# v5_mainboard_omega.net
KiCad netlist of a schematic drawn in EAGLE
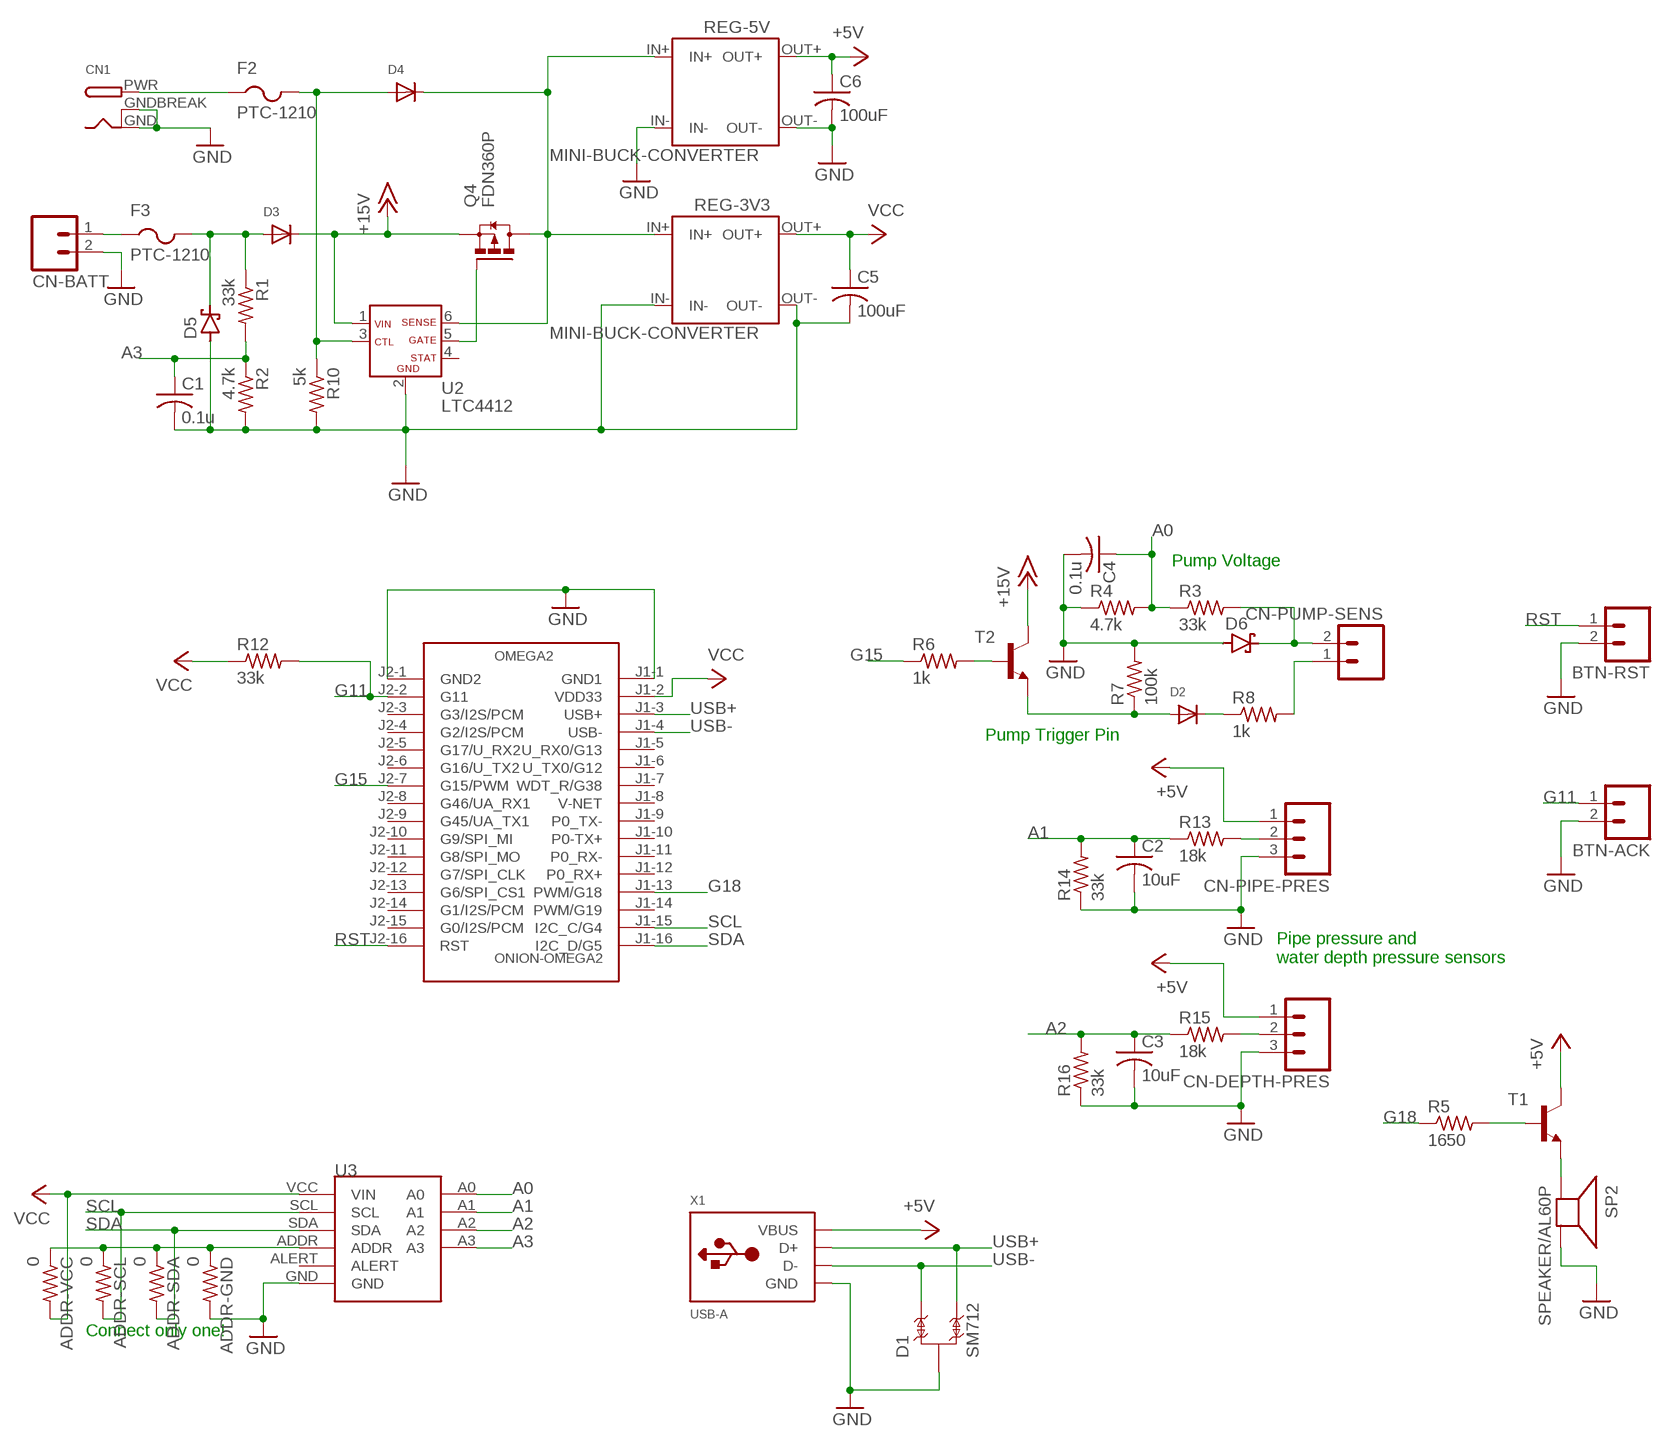
[diagram p0: schematic, sheet 1]

(export (version "E")
  (design (tool "Eeschema 10.0.6"))
  (components
    (comp (ref "ADDR-GND")
      (value "0")
      (footprint "eagle-import:R0603")
      (libsource (lib "eagle-import") (part "R-US_R0603"))
    )
    (comp (ref "ADDR-SCL")
      (value "0")
      (footprint "eagle-import:R0603")
      (libsource (lib "eagle-import") (part "R-US_R0603"))
    )
    (comp (ref "ADDR-SDA")
      (value "0")
      (footprint "eagle-import:R0603")
      (libsource (lib "eagle-import") (part "R-US_R0603"))
    )
    (comp (ref "ADDR-VCC")
      (value "0")
      (footprint "eagle-import:R0603")
      (libsource (lib "eagle-import") (part "R-US_R0603"))
    )
    (comp (ref "BTN-ACK")
      (value "M02")
      (footprint "eagle-import:02P")
      (libsource (lib "eagle-import") (part "M02"))
    )
    (comp (ref "BTN-RST")
      (value "M02")
      (footprint "eagle-import:02P")
      (libsource (lib "eagle-import") (part "M02"))
    )
    (comp (ref "C1")
      (value "0.1u")
      (footprint "eagle-import:C0603K")
      (libsource (lib "eagle-import") (part "C-USC0603K"))
    )
    (comp (ref "C2")
      (value "10uF")
      (footprint "eagle-import:C0805K")
      (libsource (lib "eagle-import") (part "C-USC0805K"))
    )
    (comp (ref "C3")
      (value "10uF")
      (footprint "eagle-import:C0805K")
      (libsource (lib "eagle-import") (part "C-USC0805K"))
    )
    (comp (ref "C4")
      (value "0.1u")
      (footprint "eagle-import:C0603K")
      (libsource (lib "eagle-import") (part "C-USC0603K"))
    )
    (comp (ref "C5")
      (value "100uF")
      (footprint "eagle-import:C2220K")
      (libsource (lib "eagle-import") (part "C-USC2220K"))
    )
    (comp (ref "C6")
      (value "100uF")
      (footprint "eagle-import:C2220K")
      (libsource (lib "eagle-import") (part "C-USC2220K"))
    )
    (comp (ref "CN-BATT")
      (value "M02")
      (footprint "eagle-import:02P")
      (libsource (lib "eagle-import") (part "M02"))
    )
    (comp (ref "CN-DEPTH-PRES")
      (value "M03")
      (footprint "eagle-import:03P")
      (libsource (lib "eagle-import") (part "M03"))
    )
    (comp (ref "CN-PIPE-PRES")
      (value "M03")
      (footprint "eagle-import:03P")
      (libsource (lib "eagle-import") (part "M03"))
    )
    (comp (ref "CN-PUMP-SENS")
      (value "M02")
      (footprint "eagle-import:02P")
      (libsource (lib "eagle-import") (part "M02"))
    )
    (comp (ref "CN1")
      (value "DCBARRELPTH")
      (footprint "eagle-import:DCJACK_2MM_PTH")
      (libsource (lib "eagle-import") (part "DCBARRELPTH"))
    )
    (comp (ref "D1")
      (value "SM712")
      (footprint "eagle-import:SOT23-3")
      (libsource (lib "eagle-import") (part "SM712"))
    )
    (comp (ref "D2")
      (value "DIODESMA")
      (footprint "eagle-import:SMADIODE")
      (libsource (lib "eagle-import") (part "DIODESMA"))
    )
    (comp (ref "D3")
      (value "DIODESMA")
      (footprint "eagle-import:SMADIODE")
      (libsource (lib "eagle-import") (part "DIODESMA"))
    )
    (comp (ref "D4")
      (value "DIODESMA")
      (footprint "eagle-import:SMADIODE")
      (libsource (lib "eagle-import") (part "DIODESMA"))
    )
    (comp (ref "D5")
      (value "SCHOTTKY-DIODESMC")
      (footprint "eagle-import:SMC")
      (libsource (lib "eagle-import") (part "SCHOTTKY-DIODESMC"))
    )
    (comp (ref "D6")
      (value "SCHOTTKY-DIODESMC")
      (footprint "eagle-import:SMC")
      (libsource (lib "eagle-import") (part "SCHOTTKY-DIODESMC"))
    )
    (comp (ref "F2")
      (value "PTC-1210")
      (footprint "eagle-import:1210")
      (libsource (lib "eagle-import") (part "PTC-1210"))
    )
    (comp (ref "F3")
      (value "PTC-1210")
      (footprint "eagle-import:1210")
      (libsource (lib "eagle-import") (part "PTC-1210"))
    )
    (comp (ref "OMEGA2")
      (value "ONION-OMEGA2")
      (footprint "eagle-import:ONION-2MM-2X16")
      (libsource (lib "eagle-import") (part "ONION-OMEGA2"))
    )
    (comp (ref "Q4")
      (value "FDN360P")
      (footprint "eagle-import:SUPER-SOT3")
      (libsource (lib "eagle-import") (part "FDN360P"))
    )
    (comp (ref "R1")
      (value "33k")
      (footprint "eagle-import:R0603")
      (libsource (lib "eagle-import") (part "R-US_R0603"))
    )
    (comp (ref "R2")
      (value "4.7k")
      (footprint "eagle-import:R0603")
      (libsource (lib "eagle-import") (part "R-US_R0603"))
    )
    (comp (ref "R3")
      (value "33k")
      (footprint "eagle-import:R0603")
      (libsource (lib "eagle-import") (part "R-US_R0603"))
    )
    (comp (ref "R4")
      (value "4.7k")
      (footprint "eagle-import:R0603")
      (libsource (lib "eagle-import") (part "R-US_R0603"))
    )
    (comp (ref "R5")
      (value "1650")
      (footprint "eagle-import:R0603")
      (libsource (lib "eagle-import") (part "R-US_R0603"))
    )
    (comp (ref "R6")
      (value "1k")
      (footprint "eagle-import:R0603")
      (libsource (lib "eagle-import") (part "R-US_R0603"))
    )
    (comp (ref "R7")
      (value "100k")
      (footprint "eagle-import:R0603")
      (libsource (lib "eagle-import") (part "R-US_R0603"))
    )
    (comp (ref "R8")
      (value "1k")
      (footprint "eagle-import:R0603")
      (libsource (lib "eagle-import") (part "R-US_R0603"))
    )
    (comp (ref "R10")
      (value "5k")
      (footprint "eagle-import:R0603")
      (libsource (lib "eagle-import") (part "R-US_R0603"))
    )
    (comp (ref "R12")
      (value "33k")
      (footprint "eagle-import:R0603")
      (libsource (lib "eagle-import") (part "R-US_R0603"))
    )
    (comp (ref "R13")
      (value "18k")
      (footprint "eagle-import:R0603")
      (libsource (lib "eagle-import") (part "R-US_R0603"))
    )
    (comp (ref "R14")
      (value "33k")
      (footprint "eagle-import:R0603")
      (libsource (lib "eagle-import") (part "R-US_R0603"))
    )
    (comp (ref "R15")
      (value "18k")
      (footprint "eagle-import:R0603")
      (libsource (lib "eagle-import") (part "R-US_R0603"))
    )
    (comp (ref "R16")
      (value "33k")
      (footprint "eagle-import:R0603")
      (libsource (lib "eagle-import") (part "R-US_R0603"))
    )
    (comp (ref "REG-3V3")
      (value "MINI-BUCK-CONVERTER")
      (footprint "eagle-import:MINI-BUCK-CONVERTER")
      (libsource (lib "eagle-import") (part "MINI-BUCK-CONVERTER"))
    )
    (comp (ref "REG-5V")
      (value "MINI-BUCK-CONVERTER")
      (footprint "eagle-import:MINI-BUCK-CONVERTER")
      (libsource (lib "eagle-import") (part "MINI-BUCK-CONVERTER"))
    )
    (comp (ref "SP2")
      (value "SPEAKER/AL60P")
      (footprint "eagle-import:AL60P")
      (libsource (lib "eagle-import") (part "SPEAKER/AL60P"))
    )
    (comp (ref "T1")
      (value "BC808-NPN-SOT23-BEC")
      (footprint "eagle-import:SOT23-BEC")
      (libsource (lib "eagle-import") (part "-NPN-SOT23-BECBC808"))
    )
    (comp (ref "T2")
      (value "BC808-NPN-SOT23-BEC")
      (footprint "eagle-import:SOT23-BEC")
      (libsource (lib "eagle-import") (part "-NPN-SOT23-BECBC808"))
    )
    (comp (ref "U2")
      (value "LTC4412")
      (footprint "eagle-import:SOT23-6")
      (libsource (lib "eagle-import") (part "LTC4412"))
    )
    (comp (ref "U3")
      (value "GY-ADS1115THM")
      (footprint "eagle-import:GY-ADS1115-THM")
      (libsource (lib "eagle-import") (part "GY-ADS1115THM"))
    )
    (comp (ref "X1")
      (value "USB-A")
      (footprint "eagle-import:MOLEX_480371000")
      (libsource (lib "eagle-import") (part "USB-A"))
    )
  )
  (nets
    (net (code "1") (name "+5V") (class "Default")
      (node (ref "C6") (pin "1") (pinfunction "1_1") (pintype "passive"))
      (node (ref "CN-DEPTH-PRES") (pin "1") (pinfunction "1_1") (pintype "passive"))
      (node (ref "CN-PIPE-PRES") (pin "1") (pinfunction "1_1") (pintype "passive"))
      (node (ref "REG-5V") (pin "OUT+") (pinfunction "OUT+_OUT+") (pintype "power_in"))
      (node (ref "T1") (pin "C") (pinfunction "C_C") (pintype "passive"))
      (node (ref "X1") (pin "1") (pinfunction "VBUS_1") (pintype "power_in"))
    )
    (net (code "2") (name "+15V") (class "Default")
      (node (ref "D3") (pin "C") (pinfunction "C_C") (pintype "passive"))
      (node (ref "Q4") (pin "2") (pinfunction "S_2") (pintype "passive"))
      (node (ref "T2") (pin "C") (pinfunction "C_C") (pintype "passive"))
      (node (ref "U2") (pin "1") (pinfunction "VIN_1") (pintype "power_in"))
    )
    (net (code "3") (name "/A0") (class "Default")
      (node (ref "C4") (pin "1") (pinfunction "1_1") (pintype "passive"))
      (node (ref "R3") (pin "1") (pinfunction "1_1") (pintype "passive"))
      (node (ref "R4") (pin "2") (pinfunction "2_2") (pintype "passive"))
      (node (ref "U3") (pin "A0") (pinfunction "A0_A0") (pintype "bidirectional"))
    )
    (net (code "4") (name "/A1") (class "Default")
      (node (ref "C2") (pin "1") (pinfunction "1_1") (pintype "passive"))
      (node (ref "R13") (pin "1") (pinfunction "1_1") (pintype "passive"))
      (node (ref "R14") (pin "2") (pinfunction "2_2") (pintype "passive"))
      (node (ref "U3") (pin "A1") (pinfunction "A1_A1") (pintype "bidirectional"))
    )
    (net (code "5") (name "/A2") (class "Default")
      (node (ref "C3") (pin "1") (pinfunction "1_1") (pintype "passive"))
      (node (ref "R15") (pin "1") (pinfunction "1_1") (pintype "passive"))
      (node (ref "R16") (pin "2") (pinfunction "2_2") (pintype "passive"))
      (node (ref "U3") (pin "A2") (pinfunction "A2_A2") (pintype "bidirectional"))
    )
    (net (code "6") (name "/A3") (class "Default")
      (node (ref "C1") (pin "1") (pinfunction "1_1") (pintype "passive"))
      (node (ref "R1") (pin "2") (pinfunction "2_2") (pintype "passive"))
      (node (ref "R2") (pin "1") (pinfunction "1_1") (pintype "passive"))
      (node (ref "U3") (pin "A3") (pinfunction "A3_A3") (pintype "bidirectional"))
    )
    (net (code "7") (name "/G11") (class "Default")
      (node (ref "BTN-ACK") (pin "1") (pinfunction "1_1") (pintype "passive"))
      (node (ref "OMEGA2") (pin "J2-2") (pinfunction "G11_J2-2") (pintype "bidirectional"))
      (node (ref "R12") (pin "2") (pinfunction "2_2") (pintype "passive"))
    )
    (net (code "8") (name "/G15") (class "Default")
      (node (ref "OMEGA2") (pin "J2-7") (pinfunction "G15/PWM_J2-7") (pintype "bidirectional"))
      (node (ref "R6") (pin "1") (pinfunction "1_1") (pintype "passive"))
    )
    (net (code "9") (name "/G18") (class "Default")
      (node (ref "OMEGA2") (pin "J1-13") (pinfunction "PWM/G18_J1-13") (pintype "bidirectional"))
      (node (ref "R5") (pin "1") (pinfunction "1_1") (pintype "passive"))
    )
    (net (code "10") (name "/RST") (class "Default")
      (node (ref "BTN-RST") (pin "1") (pinfunction "1_1") (pintype "passive"))
      (node (ref "OMEGA2") (pin "J2-16") (pinfunction "RST_J2-16") (pintype "bidirectional"))
    )
    (net (code "11") (name "/SCL") (class "Default")
      (node (ref "ADDR-SCL") (pin "2") (pinfunction "2_2") (pintype "passive"))
      (node (ref "OMEGA2") (pin "J1-15") (pinfunction "I2C_C/G4_J1-15") (pintype "bidirectional"))
      (node (ref "U3") (pin "SCL") (pinfunction "SCL_SCL") (pintype "bidirectional"))
    )
    (net (code "12") (name "/SDA") (class "Default")
      (node (ref "ADDR-SDA") (pin "2") (pinfunction "2_2") (pintype "passive"))
      (node (ref "OMEGA2") (pin "J1-16") (pinfunction "I2C_D/G5_J1-16") (pintype "bidirectional"))
      (node (ref "U3") (pin "SDA") (pinfunction "SDA_SDA") (pintype "bidirectional"))
    )
    (net (code "13") (name "/USB+") (class "Default")
      (node (ref "D1") (pin "1") (pinfunction "1_1") (pintype "passive"))
      (node (ref "OMEGA2") (pin "J1-3") (pinfunction "USB+_J1-3") (pintype "bidirectional"))
      (node (ref "X1") (pin "3") (pinfunction "D+_3") (pintype "bidirectional"))
    )
    (net (code "14") (name "/USB-") (class "Default")
      (node (ref "D1") (pin "2") (pinfunction "2_2") (pintype "passive"))
      (node (ref "OMEGA2") (pin "J1-4") (pinfunction "USB-_J1-4") (pintype "bidirectional"))
      (node (ref "X1") (pin "2") (pinfunction "D-_2") (pintype "bidirectional"))
    )
    (net (code "15") (name "GND") (class "Default")
      (node (ref "ADDR-GND") (pin "2") (pinfunction "2_2") (pintype "passive"))
      (node (ref "BTN-ACK") (pin "2") (pinfunction "2_2") (pintype "passive"))
      (node (ref "BTN-RST") (pin "2") (pinfunction "2_2") (pintype "passive"))
      (node (ref "C1") (pin "2") (pinfunction "2_2") (pintype "passive"))
      (node (ref "C2") (pin "2") (pinfunction "2_2") (pintype "passive"))
      (node (ref "C3") (pin "2") (pinfunction "2_2") (pintype "passive"))
      (node (ref "C4") (pin "2") (pinfunction "2_2") (pintype "passive"))
      (node (ref "C5") (pin "2") (pinfunction "2_2") (pintype "passive"))
      (node (ref "C6") (pin "2") (pinfunction "2_2") (pintype "passive"))
      (node (ref "CN-BATT") (pin "2") (pinfunction "2_2") (pintype "passive"))
      (node (ref "CN-DEPTH-PRES") (pin "3") (pinfunction "3_3") (pintype "passive"))
      (node (ref "CN-PIPE-PRES") (pin "3") (pinfunction "3_3") (pintype "passive"))
      (node (ref "CN1") (pin "GND") (pinfunction "GND_GND") (pintype "power_in"))
      (node (ref "CN1") (pin "GNDBREAK") (pinfunction "GNDBREAK_GNDBREAK") (pintype "power_in"))
      (node (ref "D1") (pin "3") (pinfunction "3_3") (pintype "passive"))
      (node (ref "D5") (pin "A") (pinfunction "A_A") (pintype "passive"))
      (node (ref "D6") (pin "A") (pinfunction "A_A") (pintype "passive"))
      (node (ref "OMEGA2") (pin "J1-1") (pinfunction "GND1_J1-1") (pintype "bidirectional"))
      (node (ref "OMEGA2") (pin "J2-1") (pinfunction "GND2_J2-1") (pintype "bidirectional"))
      (node (ref "R10") (pin "2") (pinfunction "2_2") (pintype "passive"))
      (node (ref "R14") (pin "1") (pinfunction "1_1") (pintype "passive"))
      (node (ref "R16") (pin "1") (pinfunction "1_1") (pintype "passive"))
      (node (ref "R2") (pin "2") (pinfunction "2_2") (pintype "passive"))
      (node (ref "R4") (pin "1") (pinfunction "1_1") (pintype "passive"))
      (node (ref "R7") (pin "2") (pinfunction "2_2") (pintype "passive"))
      (node (ref "REG-3V3") (pin "IN-") (pinfunction "IN-_IN-") (pintype "power_in"))
      (node (ref "REG-3V3") (pin "OUT-") (pinfunction "OUT-_OUT-") (pintype "power_in"))
      (node (ref "REG-5V") (pin "IN-") (pinfunction "IN-_IN-") (pintype "power_in"))
      (node (ref "REG-5V") (pin "OUT-") (pinfunction "OUT-_OUT-") (pintype "power_in"))
      (node (ref "SP2") (pin "2") (pinfunction "-_2") (pintype "passive"))
      (node (ref "U2") (pin "2") (pinfunction "GND_2") (pintype "power_in"))
      (node (ref "U3") (pin "GND") (pinfunction "GND_GND") (pintype "bidirectional"))
      (node (ref "X1") (pin "4") (pinfunction "GND_4") (pintype "power_in"))
    )
    (net (code "16") (name "Net-(ADDR-GND-Pad1)") (class "Default")
      (node (ref "ADDR-GND") (pin "1") (pinfunction "1_1") (pintype "passive"))
      (node (ref "ADDR-SCL") (pin "1") (pinfunction "1_1") (pintype "passive"))
      (node (ref "ADDR-SDA") (pin "1") (pinfunction "1_1") (pintype "passive"))
      (node (ref "ADDR-VCC") (pin "1") (pinfunction "1_1") (pintype "passive"))
      (node (ref "U3") (pin "ADDR") (pinfunction "ADDR_ADDR") (pintype "bidirectional"))
    )
    (net (code "17") (name "Net-(CN-BATT-Pad1)") (class "Default")
      (node (ref "CN-BATT") (pin "1") (pinfunction "1_1") (pintype "passive"))
      (node (ref "F3") (pin "1") (pinfunction "1_1") (pintype "passive"))
    )
    (net (code "18") (name "Net-(CN-DEPTH-PRES-Pad2)") (class "Default")
      (node (ref "CN-DEPTH-PRES") (pin "2") (pinfunction "2_2") (pintype "passive"))
      (node (ref "R15") (pin "2") (pinfunction "2_2") (pintype "passive"))
    )
    (net (code "19") (name "Net-(CN-PIPE-PRES-Pad2)") (class "Default")
      (node (ref "CN-PIPE-PRES") (pin "2") (pinfunction "2_2") (pintype "passive"))
      (node (ref "R13") (pin "2") (pinfunction "2_2") (pintype "passive"))
    )
    (net (code "20") (name "Net-(CN-PUMP-SENS-Pad1)") (class "Default")
      (node (ref "CN-PUMP-SENS") (pin "1") (pinfunction "1_1") (pintype "passive"))
      (node (ref "R8") (pin "2") (pinfunction "2_2") (pintype "passive"))
    )
    (net (code "21") (name "Net-(CN-PUMP-SENS-Pad2)") (class "Default")
      (node (ref "CN-PUMP-SENS") (pin "2") (pinfunction "2_2") (pintype "passive"))
      (node (ref "D6") (pin "C") (pinfunction "C_C") (pintype "passive"))
      (node (ref "R3") (pin "2") (pinfunction "2_2") (pintype "passive"))
    )
    (net (code "22") (name "Net-(CN1-PadPWR)") (class "Default")
      (node (ref "CN1") (pin "PWR") (pinfunction "PWR_PWR") (pintype "power_in"))
      (node (ref "F2") (pin "1") (pinfunction "1_1") (pintype "passive"))
    )
    (net (code "23") (name "Net-(D2-PadA)") (class "Default")
      (node (ref "D2") (pin "A") (pinfunction "A_A") (pintype "passive"))
      (node (ref "R7") (pin "1") (pinfunction "1_1") (pintype "passive"))
      (node (ref "T2") (pin "E") (pinfunction "E_E") (pintype "passive"))
    )
    (net (code "24") (name "Net-(D2-PadC)") (class "Default")
      (node (ref "D2") (pin "C") (pinfunction "C_C") (pintype "passive"))
      (node (ref "R8") (pin "1") (pinfunction "1_1") (pintype "passive"))
    )
    (net (code "25") (name "Net-(D3-PadA)") (class "Default")
      (node (ref "D3") (pin "A") (pinfunction "A_A") (pintype "passive"))
      (node (ref "D5") (pin "C") (pinfunction "C_C") (pintype "passive"))
      (node (ref "F3") (pin "2") (pinfunction "2_2") (pintype "passive"))
      (node (ref "R1") (pin "1") (pinfunction "1_1") (pintype "passive"))
    )
    (net (code "26") (name "Net-(Q4-D)") (class "Default")
      (node (ref "D4") (pin "C") (pinfunction "C_C") (pintype "passive"))
      (node (ref "Q4") (pin "3") (pinfunction "D_3") (pintype "passive"))
      (node (ref "REG-3V3") (pin "IN+") (pinfunction "IN+_IN+") (pintype "power_in"))
      (node (ref "REG-5V") (pin "IN+") (pinfunction "IN+_IN+") (pintype "power_in"))
      (node (ref "U2") (pin "6") (pinfunction "SENSE_6") (pintype "input"))
    )
    (net (code "27") (name "Net-(Q4-G)") (class "Default")
      (node (ref "Q4") (pin "1") (pinfunction "G_1") (pintype "passive"))
      (node (ref "U2") (pin "5") (pinfunction "GATE_5") (pintype "output"))
    )
    (net (code "28") (name "Net-(R5-Pad2)") (class "Default")
      (node (ref "R5") (pin "2") (pinfunction "2_2") (pintype "passive"))
      (node (ref "T1") (pin "B") (pinfunction "B_B") (pintype "passive"))
    )
    (net (code "29") (name "Net-(R6-Pad2)") (class "Default")
      (node (ref "R6") (pin "2") (pinfunction "2_2") (pintype "passive"))
      (node (ref "T2") (pin "B") (pinfunction "B_B") (pintype "passive"))
    )
    (net (code "30") (name "Net-(SP2-+)") (class "Default")
      (node (ref "SP2") (pin "1") (pinfunction "+_1") (pintype "passive"))
      (node (ref "T1") (pin "E") (pinfunction "E_E") (pintype "passive"))
    )
    (net (code "31") (name "Net-(U2-CTL)") (class "Default")
      (node (ref "D4") (pin "A") (pinfunction "A_A") (pintype "passive"))
      (node (ref "F2") (pin "2") (pinfunction "2_2") (pintype "passive"))
      (node (ref "R10") (pin "1") (pinfunction "1_1") (pintype "passive"))
      (node (ref "U2") (pin "3") (pinfunction "CTL_3") (pintype "input"))
    )
    (net (code "32") (name "VCC") (class "Default")
      (node (ref "ADDR-VCC") (pin "2") (pinfunction "2_2") (pintype "passive"))
      (node (ref "C5") (pin "1") (pinfunction "1_1") (pintype "passive"))
      (node (ref "OMEGA2") (pin "J1-2") (pinfunction "VDD33_J1-2") (pintype "bidirectional"))
      (node (ref "R12") (pin "1") (pinfunction "1_1") (pintype "passive"))
      (node (ref "REG-3V3") (pin "OUT+") (pinfunction "OUT+_OUT+") (pintype "power_in"))
      (node (ref "U3") (pin "VCC") (pinfunction "VIN_VCC") (pintype "bidirectional"))
    )
    (net (code "33") (name "unconnected-(OMEGA2-G0{slash}I2S{slash}PCM-PadJ2-15)") (class "Default")
      (node (ref "OMEGA2") (pin "J2-15") (pinfunction "G0/I2S/PCM_J2-15") (pintype "bidirectional"))
    )
    (net (code "34") (name "unconnected-(OMEGA2-G1{slash}I2S{slash}PCM-PadJ2-14)") (class "Default")
      (node (ref "OMEGA2") (pin "J2-14") (pinfunction "G1/I2S/PCM_J2-14") (pintype "bidirectional"))
    )
    (net (code "35") (name "unconnected-(OMEGA2-G2{slash}I2S{slash}PCM-PadJ2-4)") (class "Default")
      (node (ref "OMEGA2") (pin "J2-4") (pinfunction "G2/I2S/PCM_J2-4") (pintype "bidirectional"))
    )
    (net (code "36") (name "unconnected-(OMEGA2-G3{slash}I2S{slash}PCM-PadJ2-3)") (class "Default")
      (node (ref "OMEGA2") (pin "J2-3") (pinfunction "G3/I2S/PCM_J2-3") (pintype "bidirectional"))
    )
    (net (code "37") (name "unconnected-(OMEGA2-G6{slash}SPI_CS1-PadJ2-13)") (class "Default")
      (node (ref "OMEGA2") (pin "J2-13") (pinfunction "G6/SPI_CS1_J2-13") (pintype "bidirectional"))
    )
    (net (code "38") (name "unconnected-(OMEGA2-G7{slash}SPI_CLK-PadJ2-12)") (class "Default")
      (node (ref "OMEGA2") (pin "J2-12") (pinfunction "G7/SPI_CLK_J2-12") (pintype "bidirectional"))
    )
    (net (code "39") (name "unconnected-(OMEGA2-G8{slash}SPI_MO-PadJ2-11)") (class "Default")
      (node (ref "OMEGA2") (pin "J2-11") (pinfunction "G8/SPI_MO_J2-11") (pintype "bidirectional"))
    )
    (net (code "40") (name "unconnected-(OMEGA2-G9{slash}SPI_MI-PadJ2-10)") (class "Default")
      (node (ref "OMEGA2") (pin "J2-10") (pinfunction "G9/SPI_MI_J2-10") (pintype "bidirectional"))
    )
    (net (code "41") (name "unconnected-(OMEGA2-G16{slash}U_TX2-PadJ2-6)") (class "Default")
      (node (ref "OMEGA2") (pin "J2-6") (pinfunction "G16/U_TX2_J2-6") (pintype "bidirectional"))
    )
    (net (code "42") (name "unconnected-(OMEGA2-G17{slash}U_RX2-PadJ2-5)") (class "Default")
      (node (ref "OMEGA2") (pin "J2-5") (pinfunction "G17/U_RX2_J2-5") (pintype "bidirectional"))
    )
    (net (code "43") (name "unconnected-(OMEGA2-G45{slash}UA_TX1-PadJ2-9)") (class "Default")
      (node (ref "OMEGA2") (pin "J2-9") (pinfunction "G45/UA_TX1_J2-9") (pintype "bidirectional"))
    )
    (net (code "44") (name "unconnected-(OMEGA2-G46{slash}UA_RX1-PadJ2-8)") (class "Default")
      (node (ref "OMEGA2") (pin "J2-8") (pinfunction "G46/UA_RX1_J2-8") (pintype "bidirectional"))
    )
    (net (code "45") (name "unconnected-(OMEGA2-P0-TX+-PadJ1-10)") (class "Default")
      (node (ref "OMEGA2") (pin "J1-10") (pinfunction "P0-TX+_J1-10") (pintype "bidirectional"))
    )
    (net (code "46") (name "unconnected-(OMEGA2-P0_RX+-PadJ1-12)") (class "Default")
      (node (ref "OMEGA2") (pin "J1-12") (pinfunction "P0_RX+_J1-12") (pintype "bidirectional"))
    )
    (net (code "47") (name "unconnected-(OMEGA2-P0_RX--PadJ1-11)") (class "Default")
      (node (ref "OMEGA2") (pin "J1-11") (pinfunction "P0_RX-_J1-11") (pintype "bidirectional"))
    )
    (net (code "48") (name "unconnected-(OMEGA2-P0_TX--PadJ1-9)") (class "Default")
      (node (ref "OMEGA2") (pin "J1-9") (pinfunction "P0_TX-_J1-9") (pintype "bidirectional"))
    )
    (net (code "49") (name "unconnected-(OMEGA2-PWM{slash}G19-PadJ1-14)") (class "Default")
      (node (ref "OMEGA2") (pin "J1-14") (pinfunction "PWM/G19_J1-14") (pintype "bidirectional"))
    )
    (net (code "50") (name "unconnected-(OMEGA2-U_RX0{slash}G13-PadJ1-5)") (class "Default")
      (node (ref "OMEGA2") (pin "J1-5") (pinfunction "U_RX0/G13_J1-5") (pintype "bidirectional"))
    )
    (net (code "51") (name "unconnected-(OMEGA2-U_TX0{slash}G12-PadJ1-6)") (class "Default")
      (node (ref "OMEGA2") (pin "J1-6") (pinfunction "U_TX0/G12_J1-6") (pintype "bidirectional"))
    )
    (net (code "52") (name "unconnected-(OMEGA2-V-NET-PadJ1-8)") (class "Default")
      (node (ref "OMEGA2") (pin "J1-8") (pinfunction "V-NET_J1-8") (pintype "bidirectional"))
    )
    (net (code "53") (name "unconnected-(OMEGA2-WDT_R{slash}G38-PadJ1-7)") (class "Default")
      (node (ref "OMEGA2") (pin "J1-7") (pinfunction "WDT_R/G38_J1-7") (pintype "bidirectional"))
    )
    (net (code "54") (name "unconnected-(U2-STAT-Pad4)") (class "Default")
      (node (ref "U2") (pin "4") (pinfunction "STAT_4") (pintype "open_collector"))
    )
    (net (code "55") (name "unconnected-(U3-PadALERT)") (class "Default")
      (node (ref "U3") (pin "ALERT") (pinfunction "ALERT_ALERT") (pintype "bidirectional"))
    )
  )
)
